# Serial_Controlled_Dual_Motor_Driver-v12.net
KiCad netlist of a schematic drawn in EAGLE
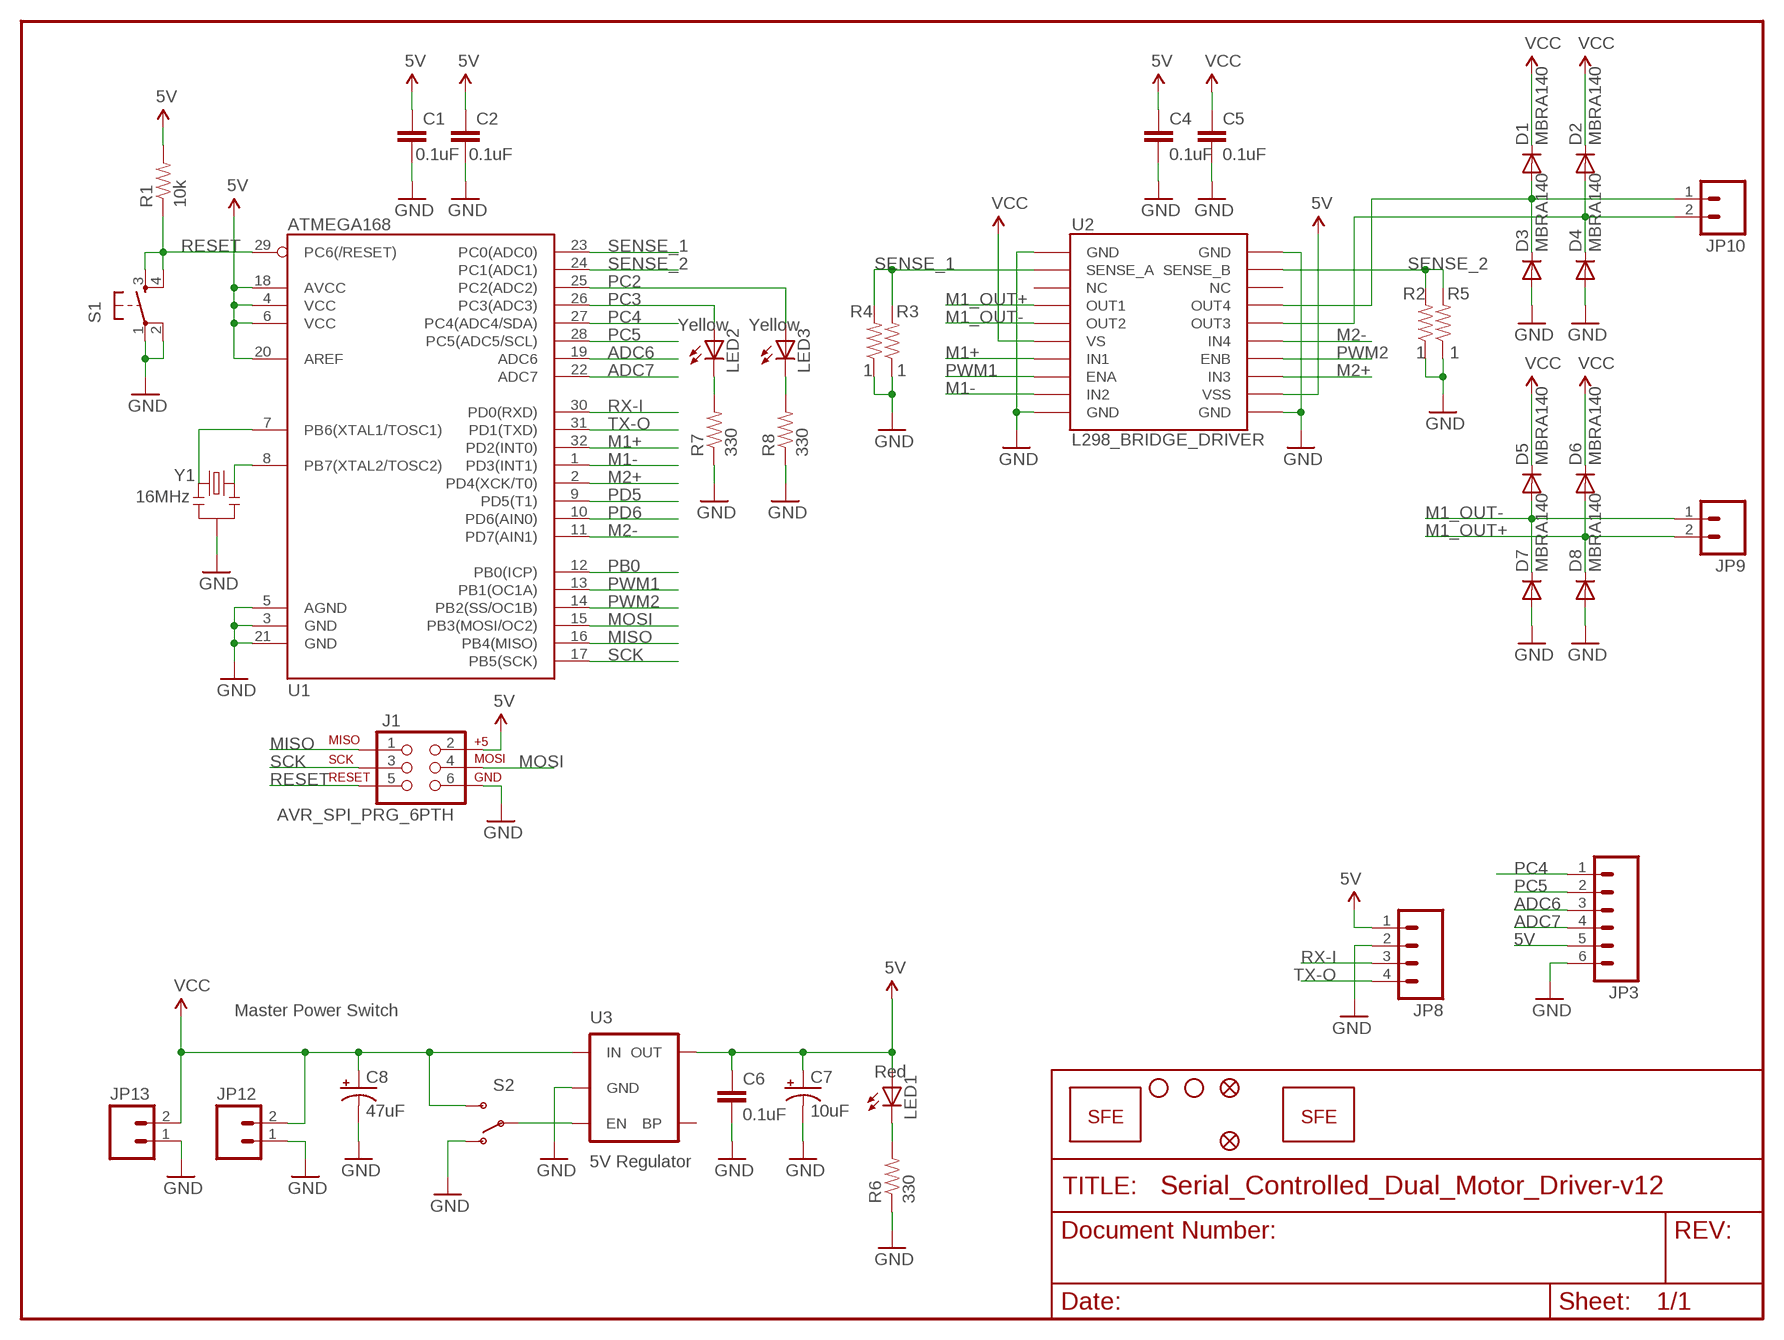
[diagram p0: schematic, sheet 1]

(export (version "E")
  (design (tool "Eeschema 10.0.6"))
  (components
    (comp (ref "C1")
      (value "0.1uF")
      (footprint "eagle-import:0603-CAP")
      (libsource (lib "eagle-import") (part "CAP0603-CAP"))
    )
    (comp (ref "C2")
      (value "0.1uF")
      (footprint "eagle-import:0603-CAP")
      (libsource (lib "eagle-import") (part "CAP0603-CAP"))
    )
    (comp (ref "C4")
      (value "0.1uF")
      (footprint "eagle-import:0603-CAP")
      (libsource (lib "eagle-import") (part "CAP0603-CAP"))
    )
    (comp (ref "C5")
      (value "0.1uF")
      (footprint "eagle-import:0603-CAP")
      (libsource (lib "eagle-import") (part "CAP0603-CAP"))
    )
    (comp (ref "C6")
      (value "0.1uF")
      (footprint "eagle-import:0603-CAP")
      (libsource (lib "eagle-import") (part "CAP0603-CAP"))
    )
    (comp (ref "C7")
      (value "10uF")
      (footprint "eagle-import:EIA3216")
      (libsource (lib "eagle-import") (part "CAP_POL1206"))
    )
    (comp (ref "C8")
      (value "47uF")
      (footprint "eagle-import:EIA3528")
      (libsource (lib "eagle-import") (part "CAP_POL3528"))
    )
    (comp (ref "D1")
      (value "MBRA140")
      (footprint "eagle-import:SMA-DIODE")
      (libsource (lib "eagle-import") (part "DIODESMA"))
    )
    (comp (ref "D2")
      (value "MBRA140")
      (footprint "eagle-import:SMA-DIODE")
      (libsource (lib "eagle-import") (part "DIODESMA"))
    )
    (comp (ref "D3")
      (value "MBRA140")
      (footprint "eagle-import:SMA-DIODE")
      (libsource (lib "eagle-import") (part "DIODESMA"))
    )
    (comp (ref "D4")
      (value "MBRA140")
      (footprint "eagle-import:SMA-DIODE")
      (libsource (lib "eagle-import") (part "DIODESMA"))
    )
    (comp (ref "D5")
      (value "MBRA140")
      (footprint "eagle-import:SMA-DIODE")
      (libsource (lib "eagle-import") (part "DIODESMA"))
    )
    (comp (ref "D6")
      (value "MBRA140")
      (footprint "eagle-import:SMA-DIODE")
      (libsource (lib "eagle-import") (part "DIODESMA"))
    )
    (comp (ref "D7")
      (value "MBRA140")
      (footprint "eagle-import:SMA-DIODE")
      (libsource (lib "eagle-import") (part "DIODESMA"))
    )
    (comp (ref "D8")
      (value "MBRA140")
      (footprint "eagle-import:SMA-DIODE")
      (libsource (lib "eagle-import") (part "DIODESMA"))
    )
    (comp (ref "J1")
      (value "AVR_SPI_PRG_6PTH")
      (footprint "eagle-import:2X3")
      (libsource (lib "eagle-import") (part "AVR_SPI_PRG_6PTH"))
    )
    (comp (ref "JP1")
      (value "LOGO-SFENEW")
      (footprint "eagle-import:SFE-NEW-WEBLOGO")
      (libsource (lib "eagle-import") (part "LOGO-SFENEW"))
    )
    (comp (ref "JP2")
      (value "STAND-OFF")
      (footprint "eagle-import:STAND-OFF")
      (libsource (lib "eagle-import") (part "STAND-OFF"))
    )
    (comp (ref "JP3")
      (value "M06SIP")
      (footprint "eagle-import:1X06")
      (libsource (lib "eagle-import") (part "M06SIP"))
    )
    (comp (ref "JP4")
      (value "FIDUCIAL1X2")
      (footprint "eagle-import:FIDUCIAL-1X2")
      (libsource (lib "eagle-import") (part "FIDUCIAL1X2"))
    )
    (comp (ref "JP5")
      (value "FIDUCIAL1X2")
      (footprint "eagle-import:FIDUCIAL-1X2")
      (libsource (lib "eagle-import") (part "FIDUCIAL1X2"))
    )
    (comp (ref "JP6")
      (value "STAND-OFF")
      (footprint "eagle-import:STAND-OFF")
      (libsource (lib "eagle-import") (part "STAND-OFF"))
    )
    (comp (ref "JP7")
      (value "LOGO-SFESK")
      (footprint "eagle-import:SFE-LOGO-FLAME")
      (libsource (lib "eagle-import") (part "LOGO-SFESK"))
    )
    (comp (ref "JP8")
      (value "M04PTH")
      (footprint "eagle-import:1X04")
      (libsource (lib "eagle-import") (part "M04PTH"))
    )
    (comp (ref "JP9")
      (value "M02PTH")
      (footprint "eagle-import:1X02")
      (libsource (lib "eagle-import") (part "M02PTH"))
    )
    (comp (ref "JP10")
      (value "M02PTH")
      (footprint "eagle-import:1X02")
      (libsource (lib "eagle-import") (part "M02PTH"))
    )
    (comp (ref "JP12")
      (value "M02-JST-2MM-SMT")
      (footprint "eagle-import:S2B-PH")
      (libsource (lib "eagle-import") (part "M02-JST-2MM-SMT"))
    )
    (comp (ref "JP13")
      (value "M02PTH")
      (footprint "eagle-import:1X02")
      (libsource (lib "eagle-import") (part "M02PTH"))
    )
    (comp (ref "LED1")
      (value "Red")
      (footprint "eagle-import:LED-0603")
      (libsource (lib "eagle-import") (part "LED0603"))
    )
    (comp (ref "LED2")
      (value "Yellow")
      (footprint "eagle-import:LED-0603")
      (libsource (lib "eagle-import") (part "LED0603"))
    )
    (comp (ref "LED3")
      (value "Yellow")
      (footprint "eagle-import:LED-0603")
      (libsource (lib "eagle-import") (part "LED0603"))
    )
    (comp (ref "R1")
      (value "10k")
      (footprint "eagle-import:0603-RES")
      (libsource (lib "eagle-import") (part "RESISTOR0603-RES"))
    )
    (comp (ref "R2")
      (value "1")
      (footprint "eagle-import:0603-RES")
      (libsource (lib "eagle-import") (part "RESISTOR0603-RES"))
    )
    (comp (ref "R3")
      (value "1")
      (footprint "eagle-import:0603-RES")
      (libsource (lib "eagle-import") (part "RESISTOR0603-RES"))
    )
    (comp (ref "R4")
      (value "1")
      (footprint "eagle-import:0603-RES")
      (libsource (lib "eagle-import") (part "RESISTOR0603-RES"))
    )
    (comp (ref "R5")
      (value "1")
      (footprint "eagle-import:0603-RES")
      (libsource (lib "eagle-import") (part "RESISTOR0603-RES"))
    )
    (comp (ref "R6")
      (value "330")
      (footprint "eagle-import:0603-RES")
      (libsource (lib "eagle-import") (part "RESISTOR0603-RES"))
    )
    (comp (ref "R7")
      (value "330")
      (footprint "eagle-import:0603-RES")
      (libsource (lib "eagle-import") (part "RESISTOR0603-RES"))
    )
    (comp (ref "R8")
      (value "330")
      (footprint "eagle-import:0603-RES")
      (libsource (lib "eagle-import") (part "RESISTOR0603-RES"))
    )
    (comp (ref "S1")
      (value "TAC_SWITCHSMD")
      (footprint "eagle-import:TACTILE_SWITCH_SMD")
      (libsource (lib "eagle-import") (part "TAC_SWITCHSMD"))
    )
    (comp (ref "S2")
      (value "SWITCH-SPSTSMD")
      (footprint "eagle-import:AYZ0202")
      (libsource (lib "eagle-import") (part "SWITCH-SPSTSMD"))
    )
    (comp (ref "U1")
      (value "ATMEGA168")
      (footprint "eagle-import:TQFP32-08")
      (libsource (lib "eagle-import") (part "ATMEGA168"))
    )
    (comp (ref "U2")
      (value "L298_BRIDGE_DRIVER")
      (footprint "eagle-import:POWERSO20")
      (libsource (lib "eagle-import") (part "L298_BRIDGE_DRIVER"))
    )
    (comp (ref "U3")
      (value "5V Regulator")
      (footprint "eagle-import:SOT23-5")
      (libsource (lib "eagle-import") (part "V_REG_LDOSMD"))
    )
    (comp (ref "Y1")
      (value "16MHz")
      (footprint "eagle-import:RESONATOR-SMD")
      (libsource (lib "eagle-import") (part "RESONATORSMD"))
    )
  )
  (nets
    (net (code "1") (name "/ADC6") (class "Default")
      (node (ref "JP3") (pin "3") (pinfunction "3_3") (pintype "passive"))
      (node (ref "U1") (pin "19") (pinfunction "ADC6_19") (pintype "bidirectional"))
    )
    (net (code "2") (name "/ADC7") (class "Default")
      (node (ref "JP3") (pin "4") (pinfunction "4_4") (pintype "passive"))
      (node (ref "U1") (pin "22") (pinfunction "ADC7_22") (pintype "bidirectional"))
    )
    (net (code "3") (name "/M1+") (class "Default")
      (node (ref "U1") (pin "32") (pinfunction "PD2(INT0)_32") (pintype "bidirectional"))
      (node (ref "U2") (pin "P$7") (pinfunction "IN1_P$7") (pintype "bidirectional"))
    )
    (net (code "4") (name "/M1-") (class "Default")
      (node (ref "U1") (pin "1") (pinfunction "PD3(INT1)_1") (pintype "bidirectional"))
      (node (ref "U2") (pin "P$9") (pinfunction "IN2_P$9") (pintype "bidirectional"))
    )
    (net (code "5") (name "/M1_OUT+") (class "Default")
      (node (ref "D6") (pin "A") (pinfunction "A_A") (pintype "passive"))
      (node (ref "D8") (pin "C") (pinfunction "C_C") (pintype "passive"))
      (node (ref "JP9") (pin "2") (pinfunction "2_2") (pintype "passive"))
      (node (ref "U2") (pin "P$4") (pinfunction "OUT1_P$4") (pintype "bidirectional"))
    )
    (net (code "6") (name "/M1_OUT-") (class "Default")
      (node (ref "D5") (pin "A") (pinfunction "A_A") (pintype "passive"))
      (node (ref "D7") (pin "C") (pinfunction "C_C") (pintype "passive"))
      (node (ref "JP9") (pin "1") (pinfunction "1_1") (pintype "passive"))
      (node (ref "U2") (pin "P$5") (pinfunction "OUT2_P$5") (pintype "bidirectional"))
    )
    (net (code "7") (name "/M2+") (class "Default")
      (node (ref "U1") (pin "2") (pinfunction "PD4(XCK/T0)_2") (pintype "bidirectional"))
      (node (ref "U2") (pin "P$13") (pinfunction "IN3_P$13") (pintype "bidirectional"))
    )
    (net (code "8") (name "/M2-") (class "Default")
      (node (ref "U1") (pin "11") (pinfunction "PD7(AIN1)_11") (pintype "bidirectional"))
      (node (ref "U2") (pin "P$15") (pinfunction "IN4_P$15") (pintype "bidirectional"))
    )
    (net (code "9") (name "/MISO") (class "Default")
      (node (ref "J1") (pin "1") (pinfunction "1_1") (pintype "passive"))
      (node (ref "U1") (pin "16") (pinfunction "PB4(MISO)_16") (pintype "bidirectional"))
    )
    (net (code "10") (name "/MOSI") (class "Default")
      (node (ref "J1") (pin "4") (pinfunction "4_4") (pintype "passive"))
      (node (ref "U1") (pin "15") (pinfunction "PB3(MOSI/OC2)_15") (pintype "bidirectional"))
    )
    (net (code "11") (name "/PB0") (class "Default")
      (node (ref "U1") (pin "12") (pinfunction "PB0(ICP)_12") (pintype "bidirectional"))
    )
    (net (code "12") (name "/PC2") (class "Default")
      (node (ref "LED3") (pin "A") (pinfunction "A_A") (pintype "passive"))
      (node (ref "U1") (pin "25") (pinfunction "PC2(ADC2)_25") (pintype "bidirectional"))
    )
    (net (code "13") (name "/PC3") (class "Default")
      (node (ref "LED2") (pin "A") (pinfunction "A_A") (pintype "passive"))
      (node (ref "U1") (pin "26") (pinfunction "PC3(ADC3)_26") (pintype "bidirectional"))
    )
    (net (code "14") (name "/PC4") (class "Default")
      (node (ref "JP3") (pin "1") (pinfunction "1_1") (pintype "passive"))
      (node (ref "U1") (pin "27") (pinfunction "PC4(ADC4/SDA)_27") (pintype "bidirectional"))
    )
    (net (code "15") (name "/PC5") (class "Default")
      (node (ref "JP3") (pin "2") (pinfunction "2_2") (pintype "passive"))
      (node (ref "U1") (pin "28") (pinfunction "PC5(ADC5/SCL)_28") (pintype "bidirectional"))
    )
    (net (code "16") (name "/PD5") (class "Default")
      (node (ref "U1") (pin "9") (pinfunction "PD5(T1)_9") (pintype "bidirectional"))
    )
    (net (code "17") (name "/PD6") (class "Default")
      (node (ref "U1") (pin "10") (pinfunction "PD6(AIN0)_10") (pintype "bidirectional"))
    )
    (net (code "18") (name "/PWM1") (class "Default")
      (node (ref "U1") (pin "13") (pinfunction "PB1(OC1A)_13") (pintype "bidirectional"))
      (node (ref "U2") (pin "P$8") (pinfunction "ENA_P$8") (pintype "bidirectional"))
    )
    (net (code "19") (name "/PWM2") (class "Default")
      (node (ref "U1") (pin "14") (pinfunction "PB2(SS/OC1B)_14") (pintype "bidirectional"))
      (node (ref "U2") (pin "P$14") (pinfunction "ENB_P$14") (pintype "bidirectional"))
    )
    (net (code "20") (name "/RESET") (class "Default")
      (node (ref "J1") (pin "5") (pinfunction "5_5") (pintype "passive"))
      (node (ref "R1") (pin "1") (pinfunction "1_1") (pintype "passive"))
      (node (ref "S1") (pin "3") (pinfunction "3_3") (pintype "passive"))
      (node (ref "S1") (pin "4") (pinfunction "4_4") (pintype "passive"))
      (node (ref "U1") (pin "29") (pinfunction "PC6(/RESET)_29") (pintype "bidirectional"))
    )
    (net (code "21") (name "/RX-I") (class "Default")
      (node (ref "JP8") (pin "3") (pinfunction "3_3") (pintype "passive"))
      (node (ref "U1") (pin "30") (pinfunction "PD0(RXD)_30") (pintype "bidirectional"))
    )
    (net (code "22") (name "/SCK") (class "Default")
      (node (ref "J1") (pin "3") (pinfunction "3_3") (pintype "passive"))
      (node (ref "U1") (pin "17") (pinfunction "PB5(SCK)_17") (pintype "bidirectional"))
    )
    (net (code "23") (name "/SENSE_1") (class "Default")
      (node (ref "R3") (pin "2") (pinfunction "2_2") (pintype "passive"))
      (node (ref "R4") (pin "2") (pinfunction "2_2") (pintype "passive"))
      (node (ref "U1") (pin "23") (pinfunction "PC0(ADC0)_23") (pintype "bidirectional"))
      (node (ref "U2") (pin "P$2") (pinfunction "SENSE_A_P$2") (pintype "bidirectional"))
    )
    (net (code "24") (name "/SENSE_2") (class "Default")
      (node (ref "R2") (pin "2") (pinfunction "2_2") (pintype "passive"))
      (node (ref "R5") (pin "2") (pinfunction "2_2") (pintype "passive"))
      (node (ref "U1") (pin "24") (pinfunction "PC1(ADC1)_24") (pintype "bidirectional"))
      (node (ref "U2") (pin "P$19") (pinfunction "SENSE_B_P$19") (pintype "bidirectional"))
    )
    (net (code "25") (name "/TX-O") (class "Default")
      (node (ref "JP8") (pin "4") (pinfunction "4_4") (pintype "passive"))
      (node (ref "U1") (pin "31") (pinfunction "PD1(TXD)_31") (pintype "bidirectional"))
    )
    (net (code "26") (name "5V") (class "Default")
      (node (ref "C1") (pin "1") (pinfunction "1_1") (pintype "passive"))
      (node (ref "C2") (pin "1") (pinfunction "1_1") (pintype "passive"))
      (node (ref "C4") (pin "1") (pinfunction "1_1") (pintype "passive"))
      (node (ref "C6") (pin "1") (pinfunction "1_1") (pintype "passive"))
      (node (ref "C7") (pin "A") (pinfunction "+_A") (pintype "passive"))
      (node (ref "J1") (pin "2") (pinfunction "2_2") (pintype "passive"))
      (node (ref "JP3") (pin "5") (pinfunction "5_5") (pintype "passive"))
      (node (ref "JP8") (pin "1") (pinfunction "1_1") (pintype "passive"))
      (node (ref "LED1") (pin "A") (pinfunction "A_A") (pintype "passive"))
      (node (ref "R1") (pin "2") (pinfunction "2_2") (pintype "passive"))
      (node (ref "U1") (pin "18") (pinfunction "AVCC_18") (pintype "bidirectional"))
      (node (ref "U1") (pin "20") (pinfunction "AREF_20") (pintype "bidirectional"))
      (node (ref "U1") (pin "4") (pinfunction "VCC_4") (pintype "bidirectional"))
      (node (ref "U1") (pin "6") (pinfunction "VCC_6") (pintype "bidirectional"))
      (node (ref "U2") (pin "P$12") (pinfunction "VSS_P$12") (pintype "bidirectional"))
      (node (ref "U3") (pin "5") (pinfunction "OUT_5") (pintype "passive"))
    )
    (net (code "27") (name "GND") (class "Default")
      (node (ref "C1") (pin "2") (pinfunction "2_2") (pintype "passive"))
      (node (ref "C2") (pin "2") (pinfunction "2_2") (pintype "passive"))
      (node (ref "C4") (pin "2") (pinfunction "2_2") (pintype "passive"))
      (node (ref "C5") (pin "2") (pinfunction "2_2") (pintype "passive"))
      (node (ref "C6") (pin "2") (pinfunction "2_2") (pintype "passive"))
      (node (ref "C7") (pin "C") (pinfunction "-_C") (pintype "passive"))
      (node (ref "C8") (pin "C") (pinfunction "-_C") (pintype "passive"))
      (node (ref "D3") (pin "A") (pinfunction "A_A") (pintype "passive"))
      (node (ref "D4") (pin "A") (pinfunction "A_A") (pintype "passive"))
      (node (ref "D7") (pin "A") (pinfunction "A_A") (pintype "passive"))
      (node (ref "D8") (pin "A") (pinfunction "A_A") (pintype "passive"))
      (node (ref "J1") (pin "6") (pinfunction "6_6") (pintype "passive"))
      (node (ref "JP12") (pin "1") (pinfunction "1_1") (pintype "passive"))
      (node (ref "JP13") (pin "1") (pinfunction "1_1") (pintype "passive"))
      (node (ref "JP3") (pin "6") (pinfunction "6_6") (pintype "passive"))
      (node (ref "JP8") (pin "2") (pinfunction "2_2") (pintype "passive"))
      (node (ref "R2") (pin "1") (pinfunction "1_1") (pintype "passive"))
      (node (ref "R3") (pin "1") (pinfunction "1_1") (pintype "passive"))
      (node (ref "R4") (pin "1") (pinfunction "1_1") (pintype "passive"))
      (node (ref "R5") (pin "1") (pinfunction "1_1") (pintype "passive"))
      (node (ref "R6") (pin "1") (pinfunction "1_1") (pintype "passive"))
      (node (ref "R7") (pin "1") (pinfunction "1_1") (pintype "passive"))
      (node (ref "R8") (pin "1") (pinfunction "1_1") (pintype "passive"))
      (node (ref "S1") (pin "1") (pinfunction "1_1") (pintype "passive"))
      (node (ref "S1") (pin "2") (pinfunction "2_2") (pintype "passive"))
      (node (ref "S2") (pin "1") (pinfunction "O_1") (pintype "passive"))
      (node (ref "U1") (pin "21") (pinfunction "GND_21") (pintype "bidirectional"))
      (node (ref "U1") (pin "3") (pinfunction "GND_3") (pintype "bidirectional"))
      (node (ref "U1") (pin "5") (pinfunction "AGND_5") (pintype "bidirectional"))
      (node (ref "U2") (pin "P$1") (pinfunction "GND_P$1") (pintype "bidirectional"))
      (node (ref "U2") (pin "P$10") (pinfunction "GND_P$10") (pintype "bidirectional"))
      (node (ref "U2") (pin "P$11") (pinfunction "GND_P$11") (pintype "bidirectional"))
      (node (ref "U2") (pin "P$20") (pinfunction "GND_P$20") (pintype "bidirectional"))
      (node (ref "U3") (pin "2") (pinfunction "GND_2") (pintype "input"))
      (node (ref "Y1") (pin "2") (pinfunction "2_2") (pintype "passive"))
    )
    (net (code "28") (name "Net-(LED1-PadC)") (class "Default")
      (node (ref "LED1") (pin "C") (pinfunction "C_C") (pintype "passive"))
      (node (ref "R6") (pin "2") (pinfunction "2_2") (pintype "passive"))
    )
    (net (code "29") (name "Net-(LED2-PadC)") (class "Default")
      (node (ref "LED2") (pin "C") (pinfunction "C_C") (pintype "passive"))
      (node (ref "R7") (pin "2") (pinfunction "2_2") (pintype "passive"))
    )
    (net (code "30") (name "Net-(LED3-PadC)") (class "Default")
      (node (ref "LED3") (pin "C") (pinfunction "C_C") (pintype "passive"))
      (node (ref "R8") (pin "2") (pinfunction "2_2") (pintype "passive"))
    )
    (net (code "31") (name "Net-(S2-P)") (class "Default")
      (node (ref "S2") (pin "2") (pinfunction "P_2") (pintype "passive"))
      (node (ref "U3") (pin "3") (pinfunction "EN_3") (pintype "input"))
    )
    (net (code "32") (name "Net-(U1-PB6(XTAL1{slash}TOSC1))") (class "Default")
      (node (ref "U1") (pin "7") (pinfunction "PB6(XTAL1/TOSC1)_7") (pintype "bidirectional"))
      (node (ref "Y1") (pin "1") (pinfunction "1_1") (pintype "passive"))
    )
    (net (code "33") (name "Net-(U1-PB7(XTAL2{slash}TOSC2))") (class "Default")
      (node (ref "U1") (pin "8") (pinfunction "PB7(XTAL2/TOSC2)_8") (pintype "bidirectional"))
      (node (ref "Y1") (pin "3") (pinfunction "3_3") (pintype "passive"))
    )
    (net (code "34") (name "Net-(U2-OUT3)") (class "Default")
      (node (ref "D2") (pin "A") (pinfunction "A_A") (pintype "passive"))
      (node (ref "D4") (pin "C") (pinfunction "C_C") (pintype "passive"))
      (node (ref "JP10") (pin "2") (pinfunction "2_2") (pintype "passive"))
      (node (ref "U2") (pin "P$16") (pinfunction "OUT3_P$16") (pintype "bidirectional"))
    )
    (net (code "35") (name "Net-(U2-OUT4)") (class "Default")
      (node (ref "D1") (pin "A") (pinfunction "A_A") (pintype "passive"))
      (node (ref "D3") (pin "C") (pinfunction "C_C") (pintype "passive"))
      (node (ref "JP10") (pin "1") (pinfunction "1_1") (pintype "passive"))
      (node (ref "U2") (pin "P$17") (pinfunction "OUT4_P$17") (pintype "bidirectional"))
    )
    (net (code "36") (name "VCC") (class "Default")
      (node (ref "C5") (pin "1") (pinfunction "1_1") (pintype "passive"))
      (node (ref "C8") (pin "A") (pinfunction "+_A") (pintype "passive"))
      (node (ref "D1") (pin "C") (pinfunction "C_C") (pintype "passive"))
      (node (ref "D2") (pin "C") (pinfunction "C_C") (pintype "passive"))
      (node (ref "D5") (pin "C") (pinfunction "C_C") (pintype "passive"))
      (node (ref "D6") (pin "C") (pinfunction "C_C") (pintype "passive"))
      (node (ref "JP12") (pin "2") (pinfunction "2_2") (pintype "passive"))
      (node (ref "JP13") (pin "2") (pinfunction "2_2") (pintype "passive"))
      (node (ref "S2") (pin "3") (pinfunction "S_3") (pintype "passive"))
      (node (ref "U2") (pin "P$6") (pinfunction "VS_P$6") (pintype "bidirectional"))
      (node (ref "U3") (pin "1") (pinfunction "IN_1") (pintype "input"))
    )
    (net (code "37") (name "unconnected-(U2-NC-PadP$3)") (class "Default")
      (node (ref "U2") (pin "P$3") (pinfunction "NC_P$3") (pintype "bidirectional"))
    )
    (net (code "38") (name "unconnected-(U2-NC-PadP$18)") (class "Default")
      (node (ref "U2") (pin "P$18") (pinfunction "NC_P$18") (pintype "bidirectional"))
    )
    (net (code "39") (name "unconnected-(U3-BP-Pad4)") (class "Default")
      (node (ref "U3") (pin "4") (pinfunction "BP_4") (pintype "input"))
    )
  )
)
